# remoteserialcontroller.net
KiCad netlist of a schematic drawn in EAGLE
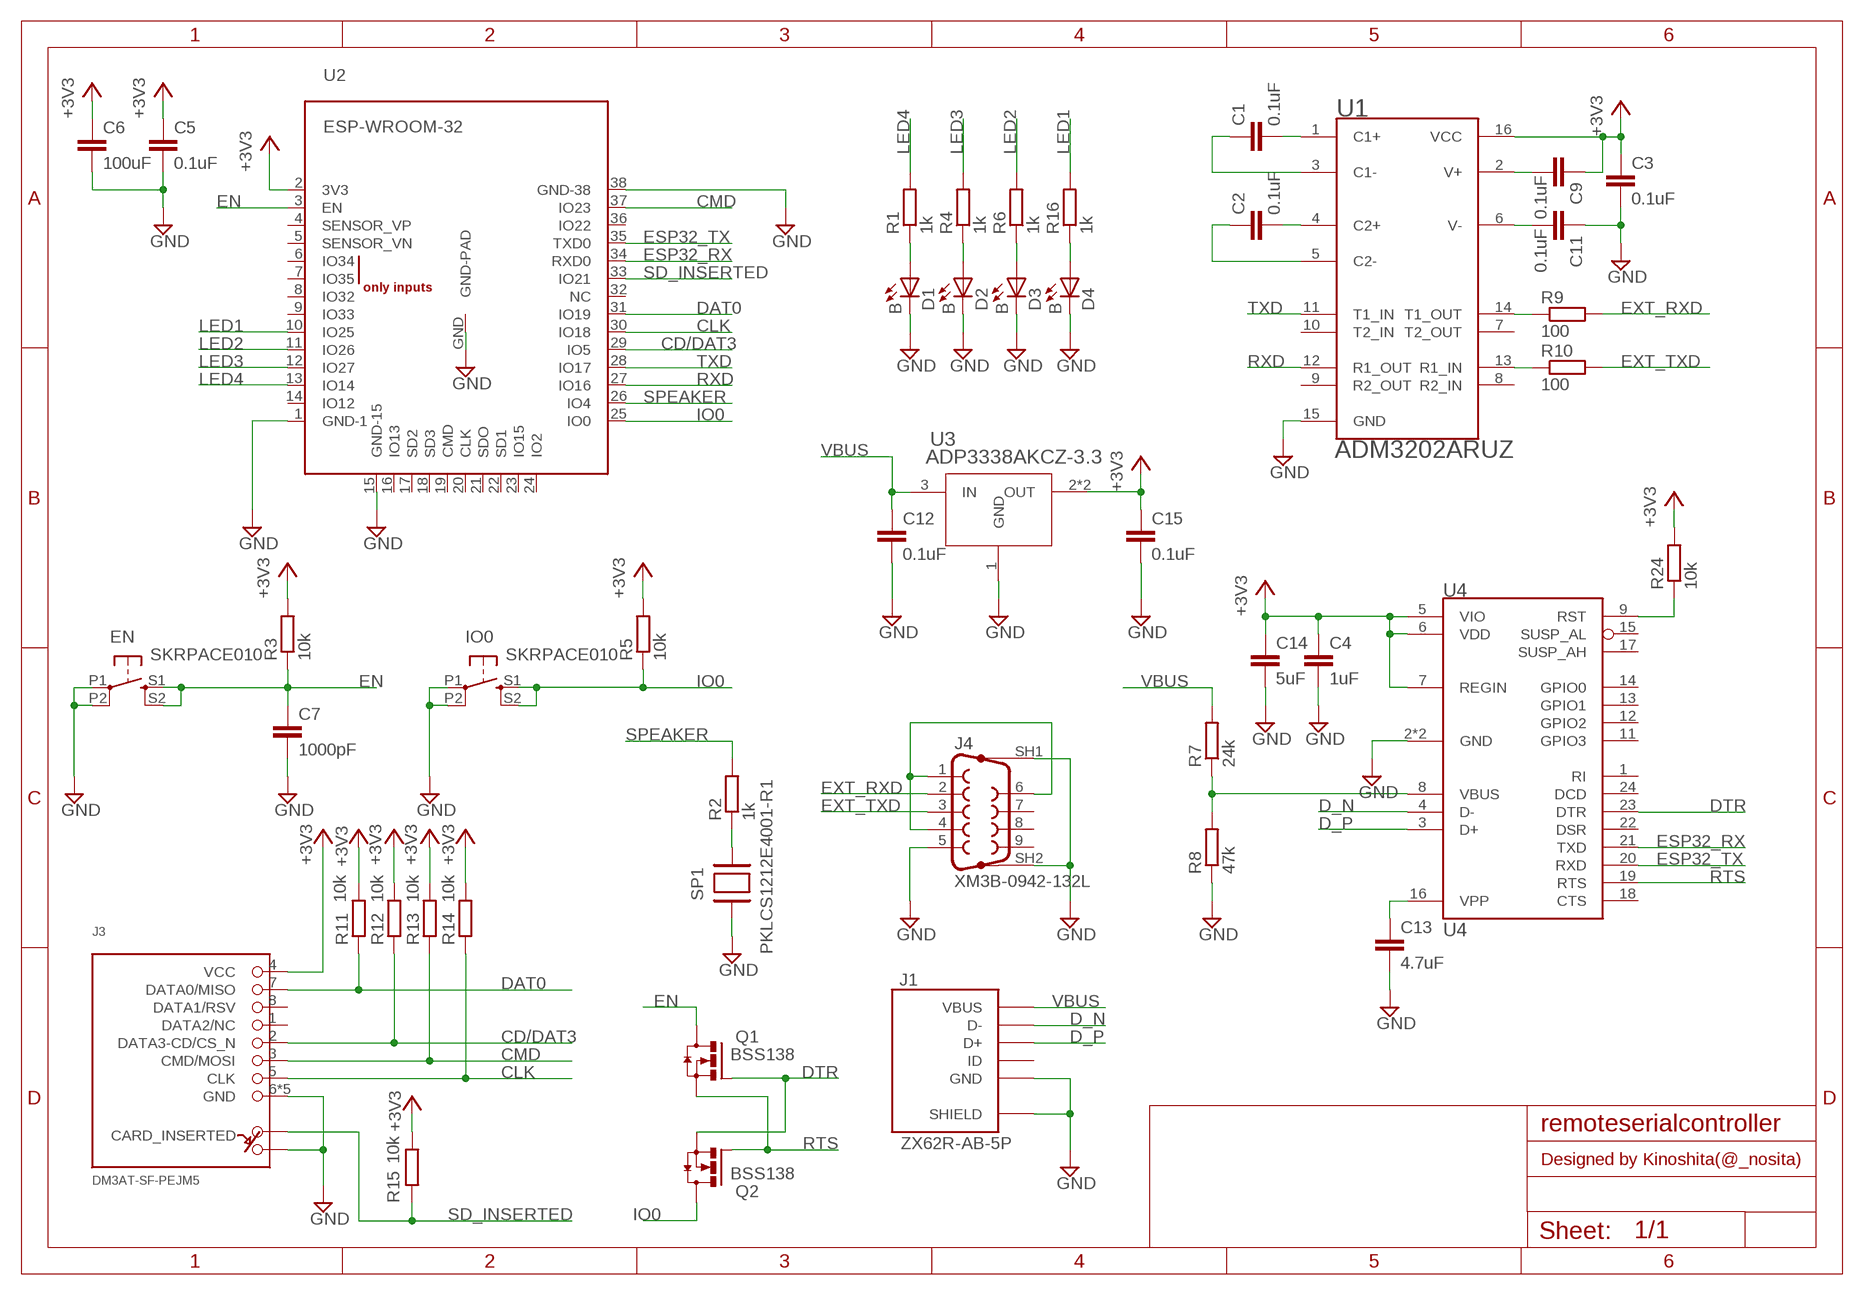
[diagram p0: schematic, sheet 1]

(export (version "E")
  (design (tool "Eeschema 10.0.6"))
  (components
    (comp (ref "C1")
      (value "0.1uF")
      (footprint "eagle-import:C0603")
      (libsource (lib "eagle-import") (part "C-EUC0603"))
    )
    (comp (ref "C2")
      (value "0.1uF")
      (footprint "eagle-import:C0603")
      (libsource (lib "eagle-import") (part "C-EUC0603"))
    )
    (comp (ref "C3")
      (value "0.1uF")
      (footprint "eagle-import:C0603")
      (libsource (lib "eagle-import") (part "C-EUC0603"))
    )
    (comp (ref "C4")
      (value "1uF")
      (footprint "eagle-import:C0603")
      (libsource (lib "eagle-import") (part "C-EUC0603"))
    )
    (comp (ref "C5")
      (value "0.1uF")
      (footprint "eagle-import:C0603")
      (libsource (lib "eagle-import") (part "C-EUC0603"))
    )
    (comp (ref "C6")
      (value "100uF")
      (footprint "eagle-import:C1210")
      (libsource (lib "eagle-import") (part "C-EUC1210"))
    )
    (comp (ref "C7")
      (value "1000pF")
      (footprint "eagle-import:C0603")
      (libsource (lib "eagle-import") (part "C-EUC0603"))
    )
    (comp (ref "C9")
      (value "0.1uF")
      (footprint "eagle-import:C0603")
      (libsource (lib "eagle-import") (part "C-EUC0603"))
    )
    (comp (ref "C11")
      (value "0.1uF")
      (footprint "eagle-import:C0603")
      (libsource (lib "eagle-import") (part "C-EUC0603"))
    )
    (comp (ref "C12")
      (value "0.1uF")
      (footprint "eagle-import:C0603")
      (libsource (lib "eagle-import") (part "C-EUC0603"))
    )
    (comp (ref "C13")
      (value "4.7uF")
      (footprint "eagle-import:C0603")
      (libsource (lib "eagle-import") (part "C-EUC0603"))
    )
    (comp (ref "C14")
      (value "5uF")
      (footprint "eagle-import:C0603")
      (libsource (lib "eagle-import") (part "C-EUC0603"))
    )
    (comp (ref "C15")
      (value "0.1uF")
      (footprint "eagle-import:C0603")
      (libsource (lib "eagle-import") (part "C-EUC0603"))
    )
    (comp (ref "D1")
      (value "B")
      (footprint "eagle-import:CHIPLED_0603")
      (libsource (lib "eagle-import") (part "LEDCHIPLED_0603"))
    )
    (comp (ref "D2")
      (value "B")
      (footprint "eagle-import:CHIPLED_0603")
      (libsource (lib "eagle-import") (part "LEDCHIPLED_0603"))
    )
    (comp (ref "D3")
      (value "B")
      (footprint "eagle-import:CHIPLED_0603")
      (libsource (lib "eagle-import") (part "LEDCHIPLED_0603"))
    )
    (comp (ref "D4")
      (value "B")
      (footprint "eagle-import:CHIPLED_0603")
      (libsource (lib "eagle-import") (part "LEDCHIPLED_0603"))
    )
    (comp (ref "EN")
      (value "SKRPACE010")
      (footprint "eagle-import:SKRPACE010")
      (libsource (lib "eagle-import") (part "SKRPACE010"))
    )
    (comp (ref "IO0")
      (value "SKRPACE010")
      (footprint "eagle-import:SKRPACE010")
      (libsource (lib "eagle-import") (part "SKRPACE010"))
    )
    (comp (ref "J1")
      (value "ZX62R-AB-5P")
      (footprint "eagle-import:ZX62R-B-5PA")
      (libsource (lib "eagle-import") (part "ZX62R-AB-5P"))
    )
    (comp (ref "J3")
      (value "DM3AT-SF-PEJM5")
      (footprint "eagle-import:DM3AT-SF-PEJM5")
      (fields (field (name "MANUFACTURER") "Hirose Electric Co Ltd"))
      (libsource (lib "eagle-import") (part "DM3AT-SF-PEJM5"))
    )
    (comp (ref "J4")
      (value "XM3B-0942-132L")
      (footprint "eagle-import:XM3B-0942-132L")
      (libsource (lib "eagle-import") (part "XM3B-0942-132L"))
    )
    (comp (ref "Q1")
      (value "BSS138")
      (footprint "eagle-import:SOT23-N-MOSFET")
      (libsource (lib "eagle-import") (part "BSS138"))
    )
    (comp (ref "Q2")
      (value "BSS138")
      (footprint "eagle-import:SOT23-N-MOSFET")
      (libsource (lib "eagle-import") (part "BSS138"))
    )
    (comp (ref "R1")
      (value "1k")
      (footprint "eagle-import:R0603")
      (libsource (lib "eagle-import") (part "R-EU_R0603"))
    )
    (comp (ref "R2")
      (value "1k")
      (footprint "eagle-import:R0603")
      (libsource (lib "eagle-import") (part "R-EU_R0603"))
    )
    (comp (ref "R3")
      (value "10k")
      (footprint "eagle-import:R0603")
      (libsource (lib "eagle-import") (part "R-EU_R0603"))
    )
    (comp (ref "R4")
      (value "1k")
      (footprint "eagle-import:R0603")
      (libsource (lib "eagle-import") (part "R-EU_R0603"))
    )
    (comp (ref "R5")
      (value "10k")
      (footprint "eagle-import:R0603")
      (libsource (lib "eagle-import") (part "R-EU_R0603"))
    )
    (comp (ref "R6")
      (value "1k")
      (footprint "eagle-import:R0603")
      (libsource (lib "eagle-import") (part "R-EU_R0603"))
    )
    (comp (ref "R7")
      (value "24k")
      (footprint "eagle-import:R0603")
      (libsource (lib "eagle-import") (part "R-EU_R0603"))
    )
    (comp (ref "R8")
      (value "47k")
      (footprint "eagle-import:R0603")
      (libsource (lib "eagle-import") (part "R-EU_R0603"))
    )
    (comp (ref "R9")
      (value "100")
      (footprint "eagle-import:R0603")
      (libsource (lib "eagle-import") (part "R-EU_R0603"))
    )
    (comp (ref "R10")
      (value "100")
      (footprint "eagle-import:R0603")
      (libsource (lib "eagle-import") (part "R-EU_R0603"))
    )
    (comp (ref "R11")
      (value "10k")
      (footprint "eagle-import:R0603")
      (libsource (lib "eagle-import") (part "R-EU_R0603"))
    )
    (comp (ref "R12")
      (value "10k")
      (footprint "eagle-import:R0603")
      (libsource (lib "eagle-import") (part "R-EU_R0603"))
    )
    (comp (ref "R13")
      (value "10k")
      (footprint "eagle-import:R0603")
      (libsource (lib "eagle-import") (part "R-EU_R0603"))
    )
    (comp (ref "R14")
      (value "10k")
      (footprint "eagle-import:R0603")
      (libsource (lib "eagle-import") (part "R-EU_R0603"))
    )
    (comp (ref "R15")
      (value "10k")
      (footprint "eagle-import:R0603")
      (libsource (lib "eagle-import") (part "R-EU_R0603"))
    )
    (comp (ref "R16")
      (value "1k")
      (footprint "eagle-import:R0603")
      (libsource (lib "eagle-import") (part "R-EU_R0603"))
    )
    (comp (ref "R24")
      (value "10k")
      (footprint "eagle-import:R0603")
      (libsource (lib "eagle-import") (part "R-EU_R0603"))
    )
    (comp (ref "SP1")
      (value "PKLCS1212E4001-R1")
      (footprint "eagle-import:PKLCS1212E4001-R1")
      (libsource (lib "eagle-import") (part "PKLCS1212E4001-R1"))
    )
    (comp (ref "U1")
      (value "ADM3202ARUZ")
      (footprint "eagle-import:TSSOP16-AD")
      (libsource (lib "eagle-import") (part "ADM3202ARUZ"))
    )
    (comp (ref "U2")
      (value "ESP-WROOM-32")
      (footprint "eagle-import:ESP-WROOM-32")
      (libsource (lib "eagle-import") (part "ESP-WROOM-32"))
    )
    (comp (ref "U3")
      (value "ADP3338AKCZ-3.3")
      (footprint "eagle-import:SOT233")
      (libsource (lib "eagle-import") (part "ADP3338AKCZ-3.3"))
    )
    (comp (ref "U4")
      (value "CP2104")
      (footprint "eagle-import:QFN24-SILABS")
      (libsource (lib "eagle-import") (part "CP2104"))
    )
  )
  (nets
    (net (code "1") (name "+3V3") (class "Default")
      (node (ref "C14") (pin "1") (pinfunction "1_1") (pintype "passive"))
      (node (ref "C15") (pin "1") (pinfunction "1_1") (pintype "passive"))
      (node (ref "C3") (pin "1") (pinfunction "1_1") (pintype "passive"))
      (node (ref "C4") (pin "1") (pinfunction "1_1") (pintype "passive"))
      (node (ref "C5") (pin "1") (pinfunction "1_1") (pintype "passive"))
      (node (ref "C6") (pin "1") (pinfunction "1_1") (pintype "passive"))
      (node (ref "C9") (pin "1") (pinfunction "1_1") (pintype "passive"))
      (node (ref "J3") (pin "4") (pinfunction "VCC_4") (pintype "bidirectional"))
      (node (ref "R11") (pin "2") (pinfunction "2_2") (pintype "passive"))
      (node (ref "R12") (pin "2") (pinfunction "2_2") (pintype "passive"))
      (node (ref "R13") (pin "2") (pinfunction "2_2") (pintype "passive"))
      (node (ref "R14") (pin "2") (pinfunction "2_2") (pintype "passive"))
      (node (ref "R15") (pin "2") (pinfunction "2_2") (pintype "passive"))
      (node (ref "R24") (pin "2") (pinfunction "2_2") (pintype "passive"))
      (node (ref "R3") (pin "2") (pinfunction "2_2") (pintype "passive"))
      (node (ref "R5") (pin "2") (pinfunction "2_2") (pintype "passive"))
      (node (ref "U1") (pin "16") (pinfunction "VCC_16") (pintype "bidirectional"))
      (node (ref "U2") (pin "2") (pinfunction "3V3_2") (pintype "bidirectional"))
      (node (ref "U3") (pin "2") (pinfunction "OUT_2") (pintype "passive"))
      (node (ref "U3") (pin "4") (pinfunction "OUT_4") (pintype "passive"))
      (node (ref "U4") (pin "5") (pinfunction "VIO_5") (pintype "bidirectional"))
      (node (ref "U4") (pin "6") (pinfunction "VDD_6") (pintype "bidirectional"))
      (node (ref "U4") (pin "7") (pinfunction "REGIN_7") (pintype "bidirectional"))
    )
    (net (code "2") (name "/CD{slash}DAT3") (class "Default")
      (node (ref "J3") (pin "2") (pinfunction "DATA3-CD/CS_N_2") (pintype "bidirectional"))
      (node (ref "R12") (pin "1") (pinfunction "1_1") (pintype "passive"))
      (node (ref "U2") (pin "29") (pinfunction "IO5_29") (pintype "bidirectional"))
    )
    (net (code "3") (name "/CLK") (class "Default")
      (node (ref "J3") (pin "5") (pinfunction "CLK_5") (pintype "bidirectional"))
      (node (ref "R14") (pin "1") (pinfunction "1_1") (pintype "passive"))
      (node (ref "U2") (pin "30") (pinfunction "IO18_30") (pintype "bidirectional"))
    )
    (net (code "4") (name "/CMD") (class "Default")
      (node (ref "J3") (pin "3") (pinfunction "CMD/MOSI_3") (pintype "bidirectional"))
      (node (ref "R13") (pin "1") (pinfunction "1_1") (pintype "passive"))
      (node (ref "U2") (pin "37") (pinfunction "IO23_37") (pintype "bidirectional"))
    )
    (net (code "5") (name "/DAT0") (class "Default")
      (node (ref "J3") (pin "7") (pinfunction "DATA0/MISO_7") (pintype "bidirectional"))
      (node (ref "R11") (pin "1") (pinfunction "1_1") (pintype "passive"))
      (node (ref "U2") (pin "31") (pinfunction "IO19_31") (pintype "bidirectional"))
    )
    (net (code "6") (name "/DTR") (class "Default")
      (node (ref "Q1") (pin "G") (pinfunction "G_G") (pintype "passive"))
      (node (ref "Q2") (pin "S") (pinfunction "S_S") (pintype "passive"))
      (node (ref "U4") (pin "23") (pinfunction "DTR_23") (pintype "bidirectional"))
    )
    (net (code "7") (name "/D_N") (class "Default")
      (node (ref "J1") (pin "D-") (pinfunction "D-_D-") (pintype "bidirectional"))
      (node (ref "U4") (pin "4") (pinfunction "D-_4") (pintype "bidirectional"))
    )
    (net (code "8") (name "/D_P") (class "Default")
      (node (ref "J1") (pin "D+") (pinfunction "D+_D+") (pintype "bidirectional"))
      (node (ref "U4") (pin "3") (pinfunction "D+_3") (pintype "bidirectional"))
    )
    (net (code "9") (name "/EN") (class "Default")
      (node (ref "C7") (pin "1") (pinfunction "1_1") (pintype "passive"))
      (node (ref "EN") (pin "S1") (pinfunction "S_S1") (pintype "passive"))
      (node (ref "EN") (pin "S2") (pinfunction "S1_S2") (pintype "passive"))
      (node (ref "Q1") (pin "D") (pinfunction "D_D") (pintype "passive"))
      (node (ref "R3") (pin "1") (pinfunction "1_1") (pintype "passive"))
      (node (ref "U2") (pin "3") (pinfunction "EN_3") (pintype "bidirectional"))
    )
    (net (code "10") (name "/ESP32_RX") (class "Default")
      (node (ref "U2") (pin "34") (pinfunction "RXD0_34") (pintype "bidirectional"))
      (node (ref "U4") (pin "21") (pinfunction "TXD_21") (pintype "bidirectional"))
    )
    (net (code "11") (name "/ESP32_TX") (class "Default")
      (node (ref "U2") (pin "35") (pinfunction "TXD0_35") (pintype "bidirectional"))
      (node (ref "U4") (pin "20") (pinfunction "RXD_20") (pintype "bidirectional"))
    )
    (net (code "12") (name "/EXT_RXD") (class "Default")
      (node (ref "J4") (pin "2") (pinfunction "2_2") (pintype "passive"))
      (node (ref "R9") (pin "2") (pinfunction "2_2") (pintype "passive"))
    )
    (net (code "13") (name "/EXT_TXD") (class "Default")
      (node (ref "J4") (pin "3") (pinfunction "3_3") (pintype "passive"))
      (node (ref "R10") (pin "2") (pinfunction "2_2") (pintype "passive"))
    )
    (net (code "14") (name "/IO0") (class "Default")
      (node (ref "IO0") (pin "S1") (pinfunction "S_S1") (pintype "passive"))
      (node (ref "IO0") (pin "S2") (pinfunction "S1_S2") (pintype "passive"))
      (node (ref "Q2") (pin "D") (pinfunction "D_D") (pintype "passive"))
      (node (ref "R5") (pin "1") (pinfunction "1_1") (pintype "passive"))
      (node (ref "U2") (pin "25") (pinfunction "IO0_25") (pintype "bidirectional"))
    )
    (net (code "15") (name "/LED1") (class "Default")
      (node (ref "R16") (pin "2") (pinfunction "2_2") (pintype "passive"))
      (node (ref "U2") (pin "10") (pinfunction "IO25_10") (pintype "bidirectional"))
    )
    (net (code "16") (name "/LED2") (class "Default")
      (node (ref "R6") (pin "2") (pinfunction "2_2") (pintype "passive"))
      (node (ref "U2") (pin "11") (pinfunction "IO26_11") (pintype "bidirectional"))
    )
    (net (code "17") (name "/LED3") (class "Default")
      (node (ref "R4") (pin "2") (pinfunction "2_2") (pintype "passive"))
      (node (ref "U2") (pin "12") (pinfunction "IO27_12") (pintype "bidirectional"))
    )
    (net (code "18") (name "/LED4") (class "Default")
      (node (ref "R1") (pin "2") (pinfunction "2_2") (pintype "passive"))
      (node (ref "U2") (pin "13") (pinfunction "IO14_13") (pintype "bidirectional"))
    )
    (net (code "19") (name "/RTS") (class "Default")
      (node (ref "Q1") (pin "S") (pinfunction "S_S") (pintype "passive"))
      (node (ref "Q2") (pin "G") (pinfunction "G_G") (pintype "passive"))
      (node (ref "U4") (pin "19") (pinfunction "RTS_19") (pintype "bidirectional"))
    )
    (net (code "20") (name "/RXD") (class "Default")
      (node (ref "U1") (pin "12") (pinfunction "R1_OUT_12") (pintype "bidirectional"))
      (node (ref "U2") (pin "27") (pinfunction "IO16_27") (pintype "bidirectional"))
    )
    (net (code "21") (name "/SD_INSERTED") (class "Default")
      (node (ref "J3") (pin "A") (pinfunction "A_A") (pintype "bidirectional"))
      (node (ref "R15") (pin "1") (pinfunction "1_1") (pintype "passive"))
      (node (ref "U2") (pin "33") (pinfunction "IO21_33") (pintype "bidirectional"))
    )
    (net (code "22") (name "/SPEAKER") (class "Default")
      (node (ref "R2") (pin "2") (pinfunction "2_2") (pintype "passive"))
      (node (ref "U2") (pin "26") (pinfunction "IO4_26") (pintype "bidirectional"))
    )
    (net (code "23") (name "/TXD") (class "Default")
      (node (ref "U1") (pin "11") (pinfunction "T1_IN_11") (pintype "bidirectional"))
      (node (ref "U2") (pin "28") (pinfunction "IO17_28") (pintype "bidirectional"))
    )
    (net (code "24") (name "/VBUS") (class "Default")
      (node (ref "C12") (pin "1") (pinfunction "1_1") (pintype "passive"))
      (node (ref "J1") (pin "VCC") (pinfunction "VBUS_VCC") (pintype "bidirectional"))
      (node (ref "R7") (pin "2") (pinfunction "2_2") (pintype "passive"))
      (node (ref "U3") (pin "3") (pinfunction "IN_3") (pintype "passive"))
    )
    (net (code "25") (name "GND") (class "Default")
      (node (ref "C11") (pin "1") (pinfunction "1_1") (pintype "passive"))
      (node (ref "C12") (pin "2") (pinfunction "2_2") (pintype "passive"))
      (node (ref "C13") (pin "2") (pinfunction "2_2") (pintype "passive"))
      (node (ref "C14") (pin "2") (pinfunction "2_2") (pintype "passive"))
      (node (ref "C15") (pin "2") (pinfunction "2_2") (pintype "passive"))
      (node (ref "C3") (pin "2") (pinfunction "2_2") (pintype "passive"))
      (node (ref "C4") (pin "2") (pinfunction "2_2") (pintype "passive"))
      (node (ref "C5") (pin "2") (pinfunction "2_2") (pintype "passive"))
      (node (ref "C6") (pin "2") (pinfunction "2_2") (pintype "passive"))
      (node (ref "C7") (pin "2") (pinfunction "2_2") (pintype "passive"))
      (node (ref "D1") (pin "C") (pinfunction "C_C") (pintype "passive"))
      (node (ref "D2") (pin "C") (pinfunction "C_C") (pintype "passive"))
      (node (ref "D3") (pin "C") (pinfunction "C_C") (pintype "passive"))
      (node (ref "D4") (pin "C") (pinfunction "C_C") (pintype "passive"))
      (node (ref "EN") (pin "P1") (pinfunction "P_P1") (pintype "passive"))
      (node (ref "EN") (pin "P2") (pinfunction "P1_P2") (pintype "passive"))
      (node (ref "IO0") (pin "P1") (pinfunction "P_P1") (pintype "passive"))
      (node (ref "IO0") (pin "P2") (pinfunction "P1_P2") (pintype "passive"))
      (node (ref "J1") (pin "GND") (pinfunction "GND_GND") (pintype "bidirectional"))
      (node (ref "J1") (pin "SHIELD@1") (pinfunction "SHIELD_SHIELD@1") (pintype "bidirectional"))
      (node (ref "J1") (pin "SHIELD@2") (pinfunction "SHIELD_SHIELD@2") (pintype "bidirectional"))
      (node (ref "J1") (pin "SHIELD@3") (pinfunction "SHIELD_SHIELD@3") (pintype "bidirectional"))
      (node (ref "J1") (pin "SHIELD@4") (pinfunction "SHIELD_SHIELD@4") (pintype "bidirectional"))
      (node (ref "J3") (pin "6") (pinfunction "GND_6") (pintype "bidirectional"))
      (node (ref "J3") (pin "B") (pinfunction "B_B") (pintype "bidirectional"))
      (node (ref "J3") (pin "MOUNT0") (pinfunction "GND_MOUNT0") (pintype "bidirectional"))
      (node (ref "J3") (pin "MOUNT1") (pinfunction "GND_MOUNT1") (pintype "bidirectional"))
      (node (ref "J3") (pin "MOUNT2") (pinfunction "GND_MOUNT2") (pintype "bidirectional"))
      (node (ref "J3") (pin "MOUNT3") (pinfunction "GND_MOUNT3") (pintype "bidirectional"))
      (node (ref "J4") (pin "5") (pinfunction "5_5") (pintype "passive"))
      (node (ref "J4") (pin "SH1") (pinfunction "G1_SH1") (pintype "passive"))
      (node (ref "J4") (pin "SH2") (pinfunction "G2_SH2") (pintype "passive"))
      (node (ref "R8") (pin "1") (pinfunction "1_1") (pintype "passive"))
      (node (ref "SP1") (pin "2") (pinfunction "P$2_2") (pintype "bidirectional"))
      (node (ref "U1") (pin "15") (pinfunction "GND_15") (pintype "bidirectional"))
      (node (ref "U2") (pin "1") (pinfunction "GND-1_1") (pintype "bidirectional"))
      (node (ref "U2") (pin "15") (pinfunction "GND-15_15") (pintype "bidirectional"))
      (node (ref "U2") (pin "38") (pinfunction "GND-38_38") (pintype "bidirectional"))
      (node (ref "U2") (pin "GND") (pinfunction "GND-PAD_GND") (pintype "bidirectional"))
      (node (ref "U3") (pin "1") (pinfunction "GND_1") (pintype "passive"))
      (node (ref "U4") (pin "2") (pinfunction "GND_2") (pintype "bidirectional"))
      (node (ref "U4") (pin "25") (pinfunction "GND_25") (pintype "bidirectional"))
    )
    (net (code "26") (name "Net-(D1-PadA)") (class "Default")
      (node (ref "D1") (pin "A") (pinfunction "A_A") (pintype "passive"))
      (node (ref "R1") (pin "1") (pinfunction "1_1") (pintype "passive"))
    )
    (net (code "27") (name "Net-(D2-PadA)") (class "Default")
      (node (ref "D2") (pin "A") (pinfunction "A_A") (pintype "passive"))
      (node (ref "R4") (pin "1") (pinfunction "1_1") (pintype "passive"))
    )
    (net (code "28") (name "Net-(D3-PadA)") (class "Default")
      (node (ref "D3") (pin "A") (pinfunction "A_A") (pintype "passive"))
      (node (ref "R6") (pin "1") (pinfunction "1_1") (pintype "passive"))
    )
    (net (code "29") (name "Net-(D4-PadA)") (class "Default")
      (node (ref "D4") (pin "A") (pinfunction "A_A") (pintype "passive"))
      (node (ref "R16") (pin "1") (pinfunction "1_1") (pintype "passive"))
    )
    (net (code "30") (name "Net-(J4-Pad1)") (class "Default")
      (node (ref "J4") (pin "1") (pinfunction "1_1") (pintype "passive"))
      (node (ref "J4") (pin "4") (pinfunction "4_4") (pintype "passive"))
      (node (ref "J4") (pin "6") (pinfunction "6_6") (pintype "passive"))
    )
    (net (code "31") (name "Net-(R2-Pad1)") (class "Default")
      (node (ref "R2") (pin "1") (pinfunction "1_1") (pintype "passive"))
      (node (ref "SP1") (pin "1") (pinfunction "1_1") (pintype "bidirectional"))
    )
    (net (code "32") (name "Net-(U1-C1+)") (class "Default")
      (node (ref "C1") (pin "2") (pinfunction "2_2") (pintype "passive"))
      (node (ref "U1") (pin "1") (pinfunction "C1+_1") (pintype "bidirectional"))
    )
    (net (code "33") (name "Net-(U1-C1-)") (class "Default")
      (node (ref "C1") (pin "1") (pinfunction "1_1") (pintype "passive"))
      (node (ref "U1") (pin "3") (pinfunction "C1-_3") (pintype "bidirectional"))
    )
    (net (code "34") (name "Net-(U1-C2+)") (class "Default")
      (node (ref "C2") (pin "2") (pinfunction "2_2") (pintype "passive"))
      (node (ref "U1") (pin "4") (pinfunction "C2+_4") (pintype "bidirectional"))
    )
    (net (code "35") (name "Net-(U1-C2-)") (class "Default")
      (node (ref "C2") (pin "1") (pinfunction "1_1") (pintype "passive"))
      (node (ref "U1") (pin "5") (pinfunction "C2-_5") (pintype "bidirectional"))
    )
    (net (code "36") (name "Net-(U1-R1_IN)") (class "Default")
      (node (ref "R10") (pin "1") (pinfunction "1_1") (pintype "passive"))
      (node (ref "U1") (pin "13") (pinfunction "R1_IN_13") (pintype "bidirectional"))
    )
    (net (code "37") (name "Net-(U1-T1_OUT)") (class "Default")
      (node (ref "R9") (pin "1") (pinfunction "1_1") (pintype "passive"))
      (node (ref "U1") (pin "14") (pinfunction "T1_OUT_14") (pintype "bidirectional"))
    )
    (net (code "38") (name "Net-(U1-V+)") (class "Default")
      (node (ref "C9") (pin "2") (pinfunction "2_2") (pintype "passive"))
      (node (ref "U1") (pin "2") (pinfunction "V+_2") (pintype "bidirectional"))
    )
    (net (code "39") (name "Net-(U1-V-)") (class "Default")
      (node (ref "C11") (pin "2") (pinfunction "2_2") (pintype "passive"))
      (node (ref "U1") (pin "6") (pinfunction "V-_6") (pintype "bidirectional"))
    )
    (net (code "40") (name "Net-(U4-RST)") (class "Default")
      (node (ref "R24") (pin "1") (pinfunction "1_1") (pintype "passive"))
      (node (ref "U4") (pin "9") (pinfunction "RST_9") (pintype "bidirectional"))
    )
    (net (code "41") (name "Net-(U4-VBUS)") (class "Default")
      (node (ref "R7") (pin "1") (pinfunction "1_1") (pintype "passive"))
      (node (ref "R8") (pin "2") (pinfunction "2_2") (pintype "passive"))
      (node (ref "U4") (pin "8") (pinfunction "VBUS_8") (pintype "bidirectional"))
    )
    (net (code "42") (name "Net-(U4-VPP)") (class "Default")
      (node (ref "C13") (pin "1") (pinfunction "1_1") (pintype "passive"))
      (node (ref "U4") (pin "16") (pinfunction "VPP_16") (pintype "bidirectional"))
    )
    (net (code "43") (name "unconnected-(J1-PadID)") (class "Default")
      (node (ref "J1") (pin "ID") (pinfunction "ID_ID") (pintype "bidirectional"))
    )
    (net (code "44") (name "unconnected-(J3-DATA1{slash}RSV-Pad8)") (class "Default")
      (node (ref "J3") (pin "8") (pinfunction "DATA1/RSV_8") (pintype "bidirectional"))
    )
    (net (code "45") (name "unconnected-(J3-DATA2{slash}NC-Pad1)") (class "Default")
      (node (ref "J3") (pin "1") (pinfunction "DATA2/NC_1") (pintype "bidirectional"))
    )
    (net (code "46") (name "unconnected-(J4-Pad7)") (class "Default")
      (node (ref "J4") (pin "7") (pinfunction "7_7") (pintype "passive"))
    )
    (net (code "47") (name "unconnected-(J4-Pad8)") (class "Default")
      (node (ref "J4") (pin "8") (pinfunction "8_8") (pintype "passive"))
    )
    (net (code "48") (name "unconnected-(J4-Pad9)") (class "Default")
      (node (ref "J4") (pin "9") (pinfunction "9_9") (pintype "passive"))
    )
    (net (code "49") (name "unconnected-(U1-R2_IN-Pad8)") (class "Default")
      (node (ref "U1") (pin "8") (pinfunction "R2_IN_8") (pintype "bidirectional"))
    )
    (net (code "50") (name "unconnected-(U1-R2_OUT-Pad9)") (class "Default")
      (node (ref "U1") (pin "9") (pinfunction "R2_OUT_9") (pintype "bidirectional"))
    )
    (net (code "51") (name "unconnected-(U1-T2_IN-Pad10)") (class "Default")
      (node (ref "U1") (pin "10") (pinfunction "T2_IN_10") (pintype "bidirectional"))
    )
    (net (code "52") (name "unconnected-(U1-T2_OUT-Pad7)") (class "Default")
      (node (ref "U1") (pin "7") (pinfunction "T2_OUT_7") (pintype "bidirectional"))
    )
    (net (code "53") (name "unconnected-(U2-CLK-Pad20)") (class "Default")
      (node (ref "U2") (pin "20") (pinfunction "CLK_20") (pintype "bidirectional"))
    )
    (net (code "54") (name "unconnected-(U2-CMD-Pad19)") (class "Default")
      (node (ref "U2") (pin "19") (pinfunction "CMD_19") (pintype "bidirectional"))
    )
    (net (code "55") (name "unconnected-(U2-IO2-Pad24)") (class "Default")
      (node (ref "U2") (pin "24") (pinfunction "IO2_24") (pintype "bidirectional"))
    )
    (net (code "56") (name "unconnected-(U2-IO12-Pad14)") (class "Default")
      (node (ref "U2") (pin "14") (pinfunction "IO12_14") (pintype "bidirectional"))
    )
    (net (code "57") (name "unconnected-(U2-IO13-Pad16)") (class "Default")
      (node (ref "U2") (pin "16") (pinfunction "IO13_16") (pintype "bidirectional"))
    )
    (net (code "58") (name "unconnected-(U2-IO15-Pad23)") (class "Default")
      (node (ref "U2") (pin "23") (pinfunction "IO15_23") (pintype "bidirectional"))
    )
    (net (code "59") (name "unconnected-(U2-IO22-Pad36)") (class "Default")
      (node (ref "U2") (pin "36") (pinfunction "IO22_36") (pintype "bidirectional"))
    )
    (net (code "60") (name "unconnected-(U2-IO32-Pad8)") (class "Default")
      (node (ref "U2") (pin "8") (pinfunction "IO32_8") (pintype "bidirectional"))
    )
    (net (code "61") (name "unconnected-(U2-IO33-Pad9)") (class "Default")
      (node (ref "U2") (pin "9") (pinfunction "IO33_9") (pintype "bidirectional"))
    )
    (net (code "62") (name "unconnected-(U2-IO34-Pad6)") (class "Default")
      (node (ref "U2") (pin "6") (pinfunction "IO34_6") (pintype "input"))
    )
    (net (code "63") (name "unconnected-(U2-IO35-Pad7)") (class "Default")
      (node (ref "U2") (pin "7") (pinfunction "IO35_7") (pintype "input"))
    )
    (net (code "64") (name "unconnected-(U2-NC-Pad32)") (class "Default")
      (node (ref "U2") (pin "32") (pinfunction "NC_32") (pintype "bidirectional"))
    )
    (net (code "65") (name "unconnected-(U2-SD1-Pad22)") (class "Default")
      (node (ref "U2") (pin "22") (pinfunction "SD1_22") (pintype "bidirectional"))
    )
    (net (code "66") (name "unconnected-(U2-SD2-Pad17)") (class "Default")
      (node (ref "U2") (pin "17") (pinfunction "SD2_17") (pintype "bidirectional"))
    )
    (net (code "67") (name "unconnected-(U2-SD3-Pad18)") (class "Default")
      (node (ref "U2") (pin "18") (pinfunction "SD3_18") (pintype "bidirectional"))
    )
    (net (code "68") (name "unconnected-(U2-SDO-Pad21)") (class "Default")
      (node (ref "U2") (pin "21") (pinfunction "SDO_21") (pintype "bidirectional"))
    )
    (net (code "69") (name "unconnected-(U2-SENSOR_VN-Pad5)") (class "Default")
      (node (ref "U2") (pin "5") (pinfunction "SENSOR_VN_5") (pintype "input"))
    )
    (net (code "70") (name "unconnected-(U2-SENSOR_VP-Pad4)") (class "Default")
      (node (ref "U2") (pin "4") (pinfunction "SENSOR_VP_4") (pintype "input"))
    )
    (net (code "71") (name "unconnected-(U4-CTS-Pad18)") (class "Default")
      (node (ref "U4") (pin "18") (pinfunction "CTS_18") (pintype "bidirectional"))
    )
    (net (code "72") (name "unconnected-(U4-DCD-Pad24)") (class "Default")
      (node (ref "U4") (pin "24") (pinfunction "DCD_24") (pintype "bidirectional"))
    )
    (net (code "73") (name "unconnected-(U4-DSR-Pad22)") (class "Default")
      (node (ref "U4") (pin "22") (pinfunction "DSR_22") (pintype "bidirectional"))
    )
    (net (code "74") (name "unconnected-(U4-GPIO0-Pad14)") (class "Default")
      (node (ref "U4") (pin "14") (pinfunction "GPIO0_14") (pintype "bidirectional"))
    )
    (net (code "75") (name "unconnected-(U4-GPIO1-Pad13)") (class "Default")
      (node (ref "U4") (pin "13") (pinfunction "GPIO1_13") (pintype "bidirectional"))
    )
    (net (code "76") (name "unconnected-(U4-GPIO2-Pad12)") (class "Default")
      (node (ref "U4") (pin "12") (pinfunction "GPIO2_12") (pintype "bidirectional"))
    )
    (net (code "77") (name "unconnected-(U4-GPIO3-Pad11)") (class "Default")
      (node (ref "U4") (pin "11") (pinfunction "GPIO3_11") (pintype "bidirectional"))
    )
    (net (code "78") (name "unconnected-(U4-RI-Pad1)") (class "Default")
      (node (ref "U4") (pin "1") (pinfunction "RI_1") (pintype "bidirectional"))
    )
    (net (code "79") (name "unconnected-(U4-SUSP_AH-Pad17)") (class "Default")
      (node (ref "U4") (pin "17") (pinfunction "SUSP_AH_17") (pintype "output"))
    )
    (net (code "80") (name "unconnected-(U4-SUSP_AL-Pad15)") (class "Default")
      (node (ref "U4") (pin "15") (pinfunction "SUSP_AL_15") (pintype "bidirectional"))
    )
  )
)
